# PCB.net
KiCad netlist of a schematic drawn in EasyEDA Pro
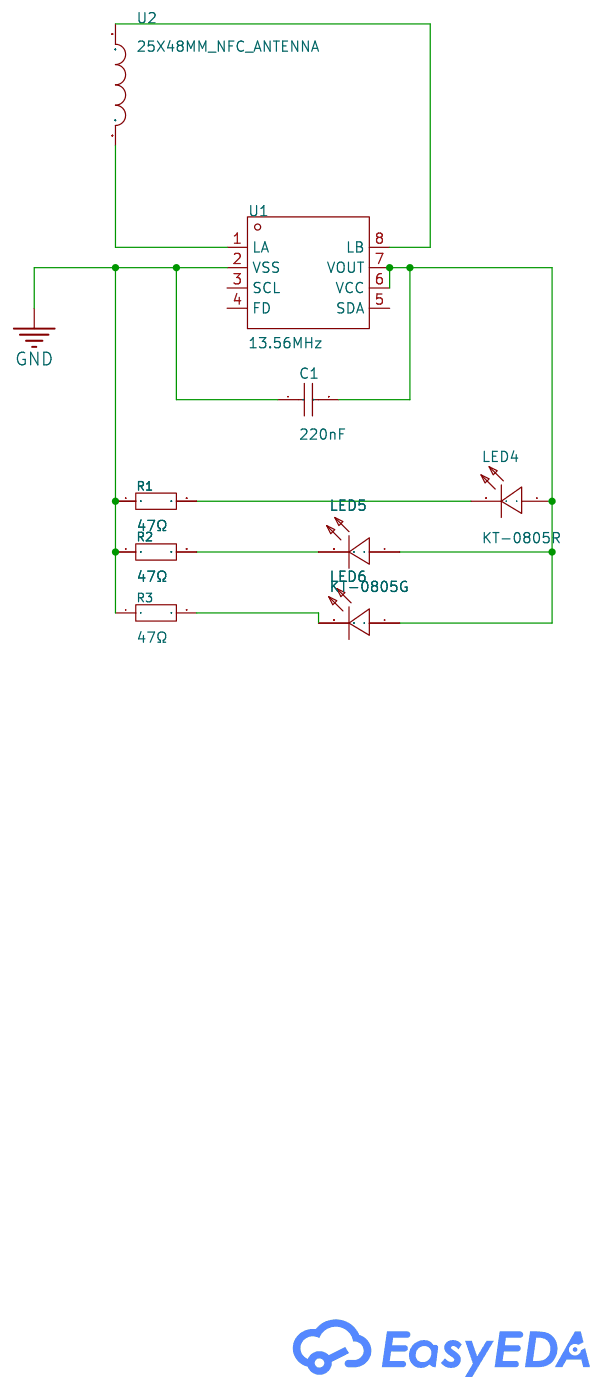
[diagram p0: schematic sheet]

(export (version "E")
  (design (tool "Eeschema 10.0.6"))
  (components
    (comp (ref "C1")
      (value "220nF")
      (footprint "easyedapro:C0603")
      (fields
        (field (name "Manufacturer Part") "CL10B224KA8NNNC")
        (field (name "Manufacturer") "SAMSUNG(三星)")
      )
      (libsource (lib "easyedapro") (part "CL10B224KA8NNNC"))
    )
    (comp (ref "LED4")
      (value "KT-0805R")
      (footprint "easyedapro:LED0805-R-RD")
      (fields (field (name "Manufacturer") "KENTO"))
      (libsource (lib "easyedapro") (part "E6C0805UR"))
    )
    (comp (ref "LED5")
      (value "KT-0805G")
      (footprint "easyedapro:LED0805-R-RD")
      (fields (field (name "Manufacturer") "KENTO"))
      (libsource (lib "easyedapro") (part "0805G (Green)"))
    )
    (comp (ref "LED6")
      (value "KT-0805B")
      (footprint "easyedapro:LED0805-R-RD")
      (fields (field (name "Manufacturer") "KENTO"))
      (libsource (lib "easyedapro") (part "XL-0805QBC"))
    )
    (comp (ref "R1")
      (value "47Ω")
      (footprint "easyedapro:R0603")
      (fields
        (field (name "Manufacturer Part") "0603WAF470JT5E")
        (field (name "Manufacturer") "UNI-ROYAL(厚声)")
      )
      (libsource (lib "easyedapro") (part "0603WAF470JT5E"))
    )
    (comp (ref "R2")
      (value "47Ω")
      (footprint "easyedapro:R0603")
      (fields
        (field (name "Manufacturer Part") "0603WAF470JT5E")
        (field (name "Manufacturer") "UNI-ROYAL(厚声)")
      )
      (libsource (lib "easyedapro") (part "0603WAF470JT5E"))
    )
    (comp (ref "R3")
      (value "47Ω")
      (footprint "easyedapro:R0603")
      (fields
        (field (name "Manufacturer Part") "0603WAF470JT5E")
        (field (name "Manufacturer") "UNI-ROYAL(厚声)")
      )
      (libsource (lib "easyedapro") (part "0603WAF470JT5E"))
    )
    (comp (ref "U1")
      (value "13.56MHz")
      (footprint "easyedapro:XQFN-8_L1.6-W1.6-P0.50-BL_NT3H2111W0FHKH")
      (fields (field (name "Manufacturer Part") "NT3H2111W0FHKH") (field (name "Manufacturer") "NXP(恩智浦)"))
      (libsource (lib "easyedapro") (part "NT3H2111W0FHKH"))
    )
    (comp (ref "U2")
      (value "25X48MM_NFC_ANTENNA")
      (footprint "easyedapro:25X48MM_NFC_ANTENNA")
      (libsource (lib "easyedapro") (part "25X48MM_NFC_ANTENNA"))
    )
  )
  (nets
    (net (code "1") (name "GND") (class "Default")
      (node (ref "C1") (pin "1") (pinfunction "1_1") (pintype "input"))
      (node (ref "R1") (pin "1") (pinfunction "1_1") (pintype "input"))
      (node (ref "R2") (pin "1") (pinfunction "1_1") (pintype "input"))
      (node (ref "R3") (pin "1") (pinfunction "1_1") (pintype "input"))
      (node (ref "U1") (pin "2") (pinfunction "VSS_2") (pintype "unspecified"))
    )
    (net (code "2") (name "Net-(LED4-A)") (class "Default")
      (node (ref "C1") (pin "2") (pinfunction "2_2") (pintype "input"))
      (node (ref "LED4") (pin "1") (pinfunction "A_1") (pintype "unspecified"))
      (node (ref "LED5") (pin "1") (pinfunction "A_1") (pintype "unspecified"))
      (node (ref "LED6") (pin "1") (pinfunction "A_1") (pintype "unspecified"))
      (node (ref "U1") (pin "6") (pinfunction "VCC_6") (pintype "unspecified"))
      (node (ref "U1") (pin "7") (pinfunction "VOUT_7") (pintype "unspecified"))
    )
    (net (code "3") (name "Net-(LED4-K)") (class "Default")
      (node (ref "LED4") (pin "2") (pinfunction "K_2") (pintype "unspecified"))
      (node (ref "R1") (pin "2") (pinfunction "2_2") (pintype "input"))
    )
    (net (code "4") (name "Net-(LED5-K)") (class "Default")
      (node (ref "LED5") (pin "2") (pinfunction "K_2") (pintype "unspecified"))
      (node (ref "R2") (pin "2") (pinfunction "2_2") (pintype "input"))
    )
    (net (code "5") (name "Net-(LED6-K)") (class "Default")
      (node (ref "LED6") (pin "2") (pinfunction "K_2") (pintype "unspecified"))
      (node (ref "R3") (pin "2") (pinfunction "2_2") (pintype "input"))
    )
    (net (code "6") (name "Net-(U1-LA)") (class "Default")
      (node (ref "U1") (pin "1") (pinfunction "LA_1") (pintype "unspecified"))
      (node (ref "U2") (pin "P$2") (pinfunction "P$2_P$2") (pintype "bidirectional"))
    )
    (net (code "7") (name "Net-(U1-LB)") (class "Default")
      (node (ref "U1") (pin "8") (pinfunction "LB_8") (pintype "unspecified"))
      (node (ref "U2") (pin "P$1") (pinfunction "P$1_P$1") (pintype "bidirectional"))
    )
    (net (code "8") (name "unconnected-(U1-FD-Pad4)") (class "Default")
      (node (ref "U1") (pin "4") (pinfunction "FD_4") (pintype "unspecified"))
    )
    (net (code "9") (name "unconnected-(U1-SCL-Pad3)") (class "Default")
      (node (ref "U1") (pin "3") (pinfunction "SCL_3") (pintype "unspecified"))
    )
    (net (code "10") (name "unconnected-(U1-SDA-Pad5)") (class "Default")
      (node (ref "U1") (pin "5") (pinfunction "SDA_5") (pintype "unspecified"))
    )
  )
)
